# PSU.net
KiCad netlist of a schematic drawn in EAGLE
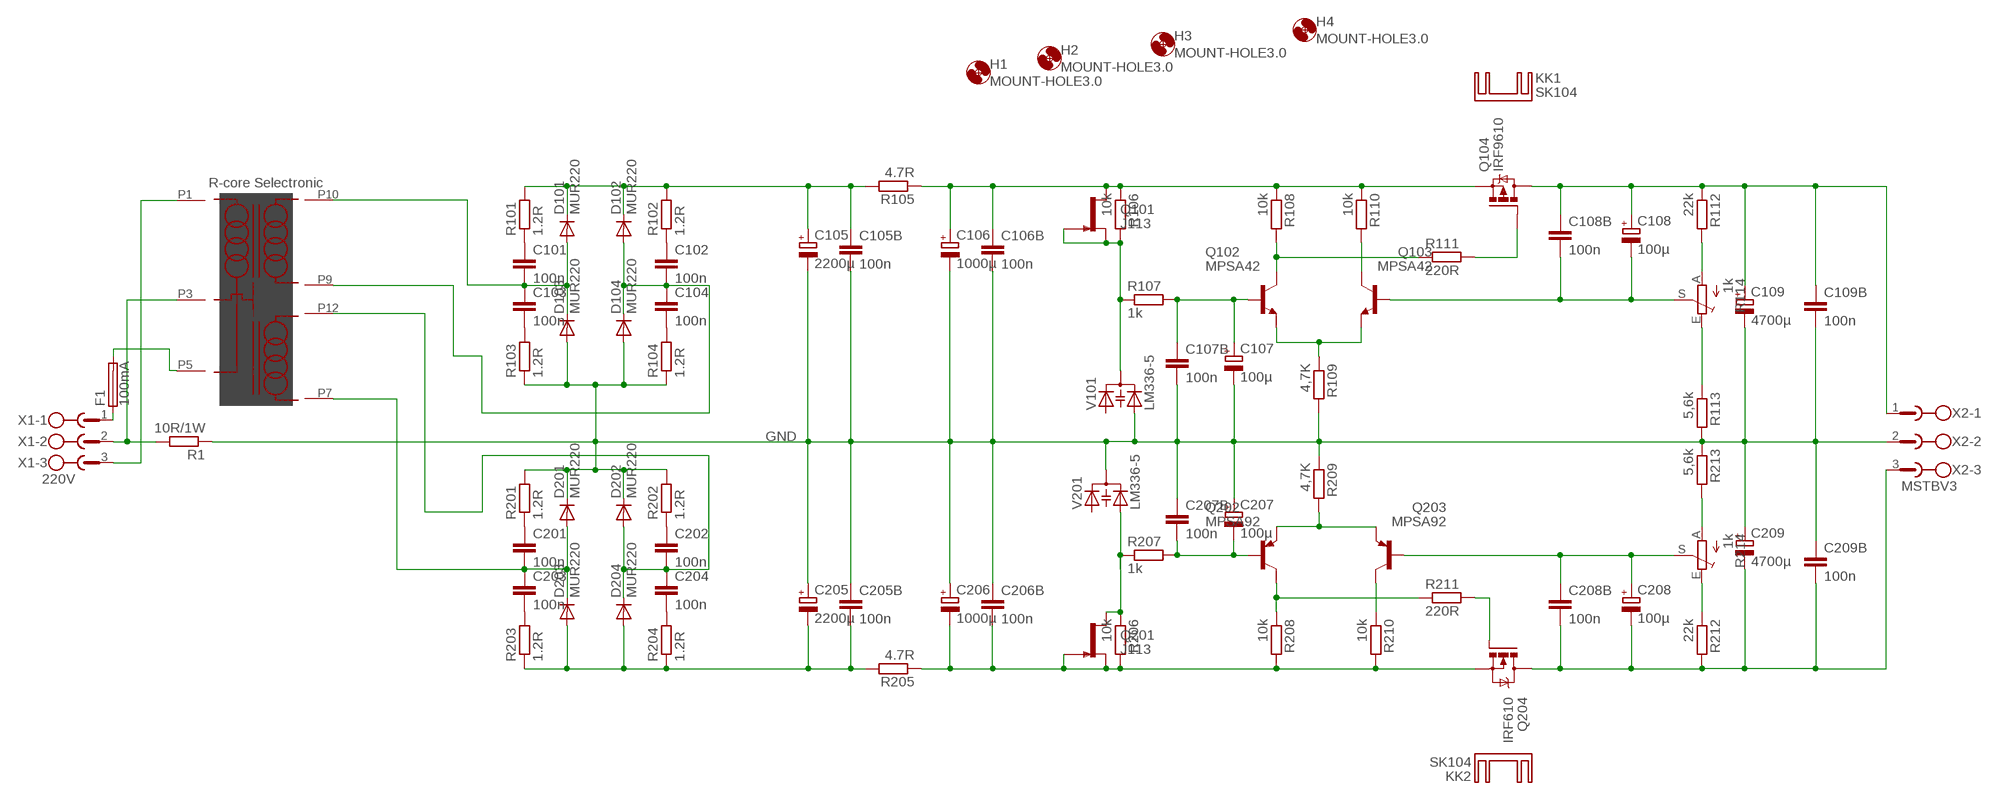
[diagram p0: schematic, sheet 1]

(export (version "E")
  (design (tool "Eeschema 10.0.6"))
  (components
    (comp (ref "C101")
      (value "100n")
      (footprint "eagle-import:C050-025X075")
      (libsource (lib "eagle-import") (part "C-EU050-025X075"))
    )
    (comp (ref "C102")
      (value "100n")
      (footprint "eagle-import:C050-025X075")
      (libsource (lib "eagle-import") (part "C-EU050-025X075"))
    )
    (comp (ref "C103")
      (value "100n")
      (footprint "eagle-import:C050-025X075")
      (libsource (lib "eagle-import") (part "C-EU050-025X075"))
    )
    (comp (ref "C104")
      (value "100n")
      (footprint "eagle-import:C050-025X075")
      (libsource (lib "eagle-import") (part "C-EU050-025X075"))
    )
    (comp (ref "C105")
      (value "2200µ")
      (footprint "eagle-import:E7,5-16")
      (libsource (lib "eagle-import") (part "CPOL-EUE7.5-16"))
    )
    (comp (ref "C105B")
      (value "100n")
      (footprint "eagle-import:C050-025X075")
      (libsource (lib "eagle-import") (part "C-EU050-025X075"))
    )
    (comp (ref "C106")
      (value "1000µ")
      (footprint "eagle-import:E7,5-16")
      (libsource (lib "eagle-import") (part "CPOL-EUE7.5-16"))
    )
    (comp (ref "C106B")
      (value "100n")
      (footprint "eagle-import:C050-025X075")
      (libsource (lib "eagle-import") (part "C-EU050-025X075"))
    )
    (comp (ref "C107")
      (value "100µ")
      (footprint "eagle-import:E5-10,5")
      (libsource (lib "eagle-import") (part "CPOL-EUE5-10.5"))
    )
    (comp (ref "C107B")
      (value "100n")
      (footprint "eagle-import:C050-025X075")
      (libsource (lib "eagle-import") (part "C-EU050-025X075"))
    )
    (comp (ref "C108")
      (value "100µ")
      (footprint "eagle-import:E5-10,5")
      (libsource (lib "eagle-import") (part "CPOL-EUE5-10.5"))
    )
    (comp (ref "C108B")
      (value "100n")
      (footprint "eagle-import:C050-025X075")
      (libsource (lib "eagle-import") (part "C-EU050-025X075"))
    )
    (comp (ref "C109")
      (value "4700µ")
      (footprint "eagle-import:EB25D")
      (libsource (lib "eagle-import") (part "CPOL-EUE10-25"))
    )
    (comp (ref "C109B")
      (value "100n")
      (footprint "eagle-import:C050-025X075")
      (libsource (lib "eagle-import") (part "C-EU050-025X075"))
    )
    (comp (ref "C201")
      (value "100n")
      (footprint "eagle-import:C050-025X075")
      (libsource (lib "eagle-import") (part "C-EU050-025X075"))
    )
    (comp (ref "C202")
      (value "100n")
      (footprint "eagle-import:C050-025X075")
      (libsource (lib "eagle-import") (part "C-EU050-025X075"))
    )
    (comp (ref "C203")
      (value "100n")
      (footprint "eagle-import:C050-025X075")
      (libsource (lib "eagle-import") (part "C-EU050-025X075"))
    )
    (comp (ref "C204")
      (value "100n")
      (footprint "eagle-import:C050-025X075")
      (libsource (lib "eagle-import") (part "C-EU050-025X075"))
    )
    (comp (ref "C205")
      (value "2200µ")
      (footprint "eagle-import:E7,5-16")
      (libsource (lib "eagle-import") (part "CPOL-EUE7.5-16"))
    )
    (comp (ref "C205B")
      (value "100n")
      (footprint "eagle-import:C050-025X075")
      (libsource (lib "eagle-import") (part "C-EU050-025X075"))
    )
    (comp (ref "C206")
      (value "1000µ")
      (footprint "eagle-import:E7,5-16")
      (libsource (lib "eagle-import") (part "CPOL-EUE7.5-16"))
    )
    (comp (ref "C206B")
      (value "100n")
      (footprint "eagle-import:C050-025X075")
      (libsource (lib "eagle-import") (part "C-EU050-025X075"))
    )
    (comp (ref "C207")
      (value "100µ")
      (footprint "eagle-import:E5-10,5")
      (libsource (lib "eagle-import") (part "CPOL-EUE5-10.5"))
    )
    (comp (ref "C207B")
      (value "100n")
      (footprint "eagle-import:C050-025X075")
      (libsource (lib "eagle-import") (part "C-EU050-025X075"))
    )
    (comp (ref "C208")
      (value "100µ")
      (footprint "eagle-import:E5-10,5")
      (libsource (lib "eagle-import") (part "CPOL-EUE5-10.5"))
    )
    (comp (ref "C208B")
      (value "100n")
      (footprint "eagle-import:C050-025X075")
      (libsource (lib "eagle-import") (part "C-EU050-025X075"))
    )
    (comp (ref "C209")
      (value "4700µ")
      (footprint "eagle-import:EB25D")
      (libsource (lib "eagle-import") (part "CPOL-EUE10-25"))
    )
    (comp (ref "C209B")
      (value "100n")
      (footprint "eagle-import:C050-025X075")
      (libsource (lib "eagle-import") (part "C-EU050-025X075"))
    )
    (comp (ref "D101")
      (value "MUR220")
      (footprint "eagle-import:DO201-15")
      (libsource (lib "eagle-import") (part "BY500"))
    )
    (comp (ref "D102")
      (value "MUR220")
      (footprint "eagle-import:DO201-15")
      (libsource (lib "eagle-import") (part "BY500"))
    )
    (comp (ref "D103")
      (value "MUR220")
      (footprint "eagle-import:DO201-15")
      (libsource (lib "eagle-import") (part "BY500"))
    )
    (comp (ref "D104")
      (value "MUR220")
      (footprint "eagle-import:DO201-15")
      (libsource (lib "eagle-import") (part "BY500"))
    )
    (comp (ref "D201")
      (value "MUR220")
      (footprint "eagle-import:DO201-15")
      (libsource (lib "eagle-import") (part "BY500"))
    )
    (comp (ref "D202")
      (value "MUR220")
      (footprint "eagle-import:DO201-15")
      (libsource (lib "eagle-import") (part "BY500"))
    )
    (comp (ref "D203")
      (value "MUR220")
      (footprint "eagle-import:DO201-15")
      (libsource (lib "eagle-import") (part "BY500"))
    )
    (comp (ref "D204")
      (value "MUR220")
      (footprint "eagle-import:DO201-15")
      (libsource (lib "eagle-import") (part "BY500"))
    )
    (comp (ref "F1")
      (value "100mA")
      (footprint "eagle-import:GSH15")
      (fields (field (name "MPN") "64900001039"))
      (libsource (lib "eagle-import") (part "GSH15"))
    )
    (comp (ref "H1")
      (value "MOUNT-HOLE3.0")
      (footprint "eagle-import:3,0")
      (libsource (lib "eagle-import") (part "MOUNT-HOLE3.0"))
    )
    (comp (ref "H2")
      (value "MOUNT-HOLE3.0")
      (footprint "eagle-import:3,0")
      (libsource (lib "eagle-import") (part "MOUNT-HOLE3.0"))
    )
    (comp (ref "H3")
      (value "MOUNT-HOLE3.0")
      (footprint "eagle-import:3,0")
      (libsource (lib "eagle-import") (part "MOUNT-HOLE3.0"))
    )
    (comp (ref "H4")
      (value "MOUNT-HOLE3.0")
      (footprint "eagle-import:3,0")
      (libsource (lib "eagle-import") (part "MOUNT-HOLE3.0"))
    )
    (comp (ref "KK1")
      (value "SK104")
      (footprint "eagle-import:SK104")
      (libsource (lib "eagle-import") (part "SK104"))
    )
    (comp (ref "KK2")
      (value "SK104")
      (footprint "eagle-import:SK104")
      (libsource (lib "eagle-import") (part "SK104"))
    )
    (comp (ref "Q101")
      (value "J113")
      (footprint "eagle-import:TO-92")
      (libsource (lib "eagle-import") (part "2N5458"))
    )
    (comp (ref "Q102")
      (value "MPSA42")
      (footprint "eagle-import:TO92-EBC")
      (libsource (lib "eagle-import") (part "-NPN-TO92-EBC"))
    )
    (comp (ref "Q103")
      (value "MPSA42")
      (footprint "eagle-import:TO92-EBC")
      (libsource (lib "eagle-import") (part "-NPN-TO92-EBC"))
    )
    (comp (ref "Q104")
      (value "IRF9610")
      (footprint "eagle-import:TO220BV")
      (libsource (lib "eagle-import") (part "IRF9530"))
    )
    (comp (ref "Q201")
      (value "J113")
      (footprint "eagle-import:TO-92")
      (libsource (lib "eagle-import") (part "2N5458"))
    )
    (comp (ref "Q202")
      (value "MPSA92")
      (footprint "eagle-import:TO92-EBC")
      (libsource (lib "eagle-import") (part "-PNP-TO92-EBCBCX58"))
    )
    (comp (ref "Q203")
      (value "MPSA92")
      (footprint "eagle-import:TO92-EBC")
      (libsource (lib "eagle-import") (part "-PNP-TO92-EBCBCX58"))
    )
    (comp (ref "Q204")
      (value "IRF610")
      (footprint "eagle-import:TO220BV")
      (libsource (lib "eagle-import") (part "IRF740"))
    )
    (comp (ref "R1")
      (value "10R/1W")
      (footprint "eagle-import:P0613_15")
      (libsource (lib "eagle-import") (part "R-EU_0613/15"))
    )
    (comp (ref "R101")
      (value "1.2R")
      (footprint "eagle-import:0207_10")
      (libsource (lib "eagle-import") (part "R-EU_0207/10"))
    )
    (comp (ref "R102")
      (value "1.2R")
      (footprint "eagle-import:0207_10")
      (libsource (lib "eagle-import") (part "R-EU_0207/10"))
    )
    (comp (ref "R103")
      (value "1.2R")
      (footprint "eagle-import:0207_10")
      (libsource (lib "eagle-import") (part "R-EU_0207/10"))
    )
    (comp (ref "R104")
      (value "1.2R")
      (footprint "eagle-import:0207_10")
      (libsource (lib "eagle-import") (part "R-EU_0207/10"))
    )
    (comp (ref "R105")
      (value "4.7R")
      (footprint "eagle-import:0207_10")
      (libsource (lib "eagle-import") (part "R-EU_0207/10"))
    )
    (comp (ref "R106")
      (value "10k")
      (footprint "eagle-import:0207_10")
      (libsource (lib "eagle-import") (part "R-EU_0207/10"))
    )
    (comp (ref "R107")
      (value "1k")
      (footprint "eagle-import:0207_10")
      (libsource (lib "eagle-import") (part "R-EU_0207/10"))
    )
    (comp (ref "R108")
      (value "10k")
      (footprint "eagle-import:0207_10")
      (libsource (lib "eagle-import") (part "R-EU_0207/10"))
    )
    (comp (ref "R109")
      (value "4,7K")
      (footprint "eagle-import:0207_10")
      (libsource (lib "eagle-import") (part "R-EU_0207/10"))
    )
    (comp (ref "R110")
      (value "10k")
      (footprint "eagle-import:0207_10")
      (libsource (lib "eagle-import") (part "R-EU_0207/10"))
    )
    (comp (ref "R111")
      (value "220R")
      (footprint "eagle-import:0207_10")
      (libsource (lib "eagle-import") (part "R-EU_0207/10"))
    )
    (comp (ref "R112")
      (value "22k")
      (footprint "eagle-import:0207_10")
      (libsource (lib "eagle-import") (part "R-EU_0207/10"))
    )
    (comp (ref "R113")
      (value "5,6k")
      (footprint "eagle-import:0207_10")
      (libsource (lib "eagle-import") (part "R-EU_0207/10"))
    )
    (comp (ref "R114")
      (value "1k")
      (footprint "eagle-import:S64W")
      (libsource (lib "eagle-import") (part "TRIM_EU-S64W"))
    )
    (comp (ref "R201")
      (value "1.2R")
      (footprint "eagle-import:0207_10")
      (libsource (lib "eagle-import") (part "R-EU_0207/10"))
    )
    (comp (ref "R202")
      (value "1.2R")
      (footprint "eagle-import:0207_10")
      (libsource (lib "eagle-import") (part "R-EU_0207/10"))
    )
    (comp (ref "R203")
      (value "1.2R")
      (footprint "eagle-import:0207_10")
      (libsource (lib "eagle-import") (part "R-EU_0207/10"))
    )
    (comp (ref "R204")
      (value "1.2R")
      (footprint "eagle-import:0207_10")
      (libsource (lib "eagle-import") (part "R-EU_0207/10"))
    )
    (comp (ref "R205")
      (value "4.7R")
      (footprint "eagle-import:0207_10")
      (libsource (lib "eagle-import") (part "R-EU_0207/10"))
    )
    (comp (ref "R206")
      (value "10k")
      (footprint "eagle-import:0207_10")
      (libsource (lib "eagle-import") (part "R-EU_0207/10"))
    )
    (comp (ref "R207")
      (value "1k")
      (footprint "eagle-import:0207_10")
      (libsource (lib "eagle-import") (part "R-EU_0207/10"))
    )
    (comp (ref "R208")
      (value "10k")
      (footprint "eagle-import:0207_10")
      (libsource (lib "eagle-import") (part "R-EU_0207/10"))
    )
    (comp (ref "R209")
      (value "4,7K")
      (footprint "eagle-import:0207_10")
      (libsource (lib "eagle-import") (part "R-EU_0207/10"))
    )
    (comp (ref "R210")
      (value "10k")
      (footprint "eagle-import:0207_10")
      (libsource (lib "eagle-import") (part "R-EU_0207/10"))
    )
    (comp (ref "R211")
      (value "220R")
      (footprint "eagle-import:0207_10")
      (libsource (lib "eagle-import") (part "R-EU_0207/10"))
    )
    (comp (ref "R212")
      (value "22k")
      (footprint "eagle-import:0207_10")
      (libsource (lib "eagle-import") (part "R-EU_0207/10"))
    )
    (comp (ref "R213")
      (value "5,6k")
      (footprint "eagle-import:0207_10")
      (libsource (lib "eagle-import") (part "R-EU_0207/10"))
    )
    (comp (ref "R214")
      (value "1k")
      (footprint "eagle-import:S64W")
      (libsource (lib "eagle-import") (part "TRIM_EU-S64W"))
    )
    (comp (ref "U$1")
      (value "R-CORE-SELECTRONIC-PCB")
      (footprint "eagle-import:R-CORE48MM")
      (libsource (lib "eagle-import") (part "R-CORE-SELECTRONIC-PCB"))
    )
    (comp (ref "V101")
      (value "LM336-5")
      (footprint "eagle-import:SOT54E")
      (libsource (lib "eagle-import") (part "DIODE-2CAPACITANCESOT54E"))
    )
    (comp (ref "V201")
      (value "LM336-5")
      (footprint "eagle-import:SOT54E")
      (libsource (lib "eagle-import") (part "DIODE-2CAPACITANCESOT54E"))
    )
    (comp (ref "X1")
      (value "220V")
      (footprint "eagle-import:MSTBV3")
      (fields (field (name "MPN") "MSTBV 2,5/3-GF-5.08"))
      (libsource (lib "eagle-import") (part "MSTBV3"))
    )
    (comp (ref "X2")
      (value "MSTBV3")
      (footprint "eagle-import:MSTBV3")
      (fields (field (name "MPN") "MSTBV 2,5/3-GF-5.08"))
      (libsource (lib "eagle-import") (part "MSTBV3"))
    )
  )
  (nets
    (net (code "1") (name "/GND") (class "Default")
      (node (ref "C105") (pin "-") (pinfunction "-_-") (pintype "passive"))
      (node (ref "C105B") (pin "2") (pinfunction "2_2") (pintype "passive"))
      (node (ref "C106") (pin "-") (pinfunction "-_-") (pintype "passive"))
      (node (ref "C106B") (pin "2") (pinfunction "2_2") (pintype "passive"))
      (node (ref "C107") (pin "-") (pinfunction "-_-") (pintype "passive"))
      (node (ref "C107B") (pin "2") (pinfunction "2_2") (pintype "passive"))
      (node (ref "C109") (pin "-") (pinfunction "-_-") (pintype "passive"))
      (node (ref "C109B") (pin "2") (pinfunction "2_2") (pintype "passive"))
      (node (ref "C205") (pin "+") (pinfunction "+_+") (pintype "passive"))
      (node (ref "C205B") (pin "1") (pinfunction "1_1") (pintype "passive"))
      (node (ref "C206") (pin "+") (pinfunction "+_+") (pintype "passive"))
      (node (ref "C206B") (pin "1") (pinfunction "1_1") (pintype "passive"))
      (node (ref "C207") (pin "+") (pinfunction "+_+") (pintype "passive"))
      (node (ref "C207B") (pin "1") (pinfunction "1_1") (pintype "passive"))
      (node (ref "C209") (pin "+") (pinfunction "+_+") (pintype "passive"))
      (node (ref "C209B") (pin "1") (pinfunction "1_1") (pintype "passive"))
      (node (ref "D103") (pin "A") (pinfunction "A_A") (pintype "passive"))
      (node (ref "D104") (pin "A") (pinfunction "A_A") (pintype "passive"))
      (node (ref "D201") (pin "C") (pinfunction "C_C") (pintype "passive"))
      (node (ref "D202") (pin "C") (pinfunction "C_C") (pintype "passive"))
      (node (ref "R1") (pin "1") (pinfunction "1_1") (pintype "passive"))
      (node (ref "R103") (pin "1") (pinfunction "1_1") (pintype "passive"))
      (node (ref "R104") (pin "1") (pinfunction "1_1") (pintype "passive"))
      (node (ref "R109") (pin "2") (pinfunction "2_2") (pintype "passive"))
      (node (ref "R113") (pin "2") (pinfunction "2_2") (pintype "passive"))
      (node (ref "R201") (pin "2") (pinfunction "2_2") (pintype "passive"))
      (node (ref "R202") (pin "2") (pinfunction "2_2") (pintype "passive"))
      (node (ref "R209") (pin "1") (pinfunction "1_1") (pintype "passive"))
      (node (ref "R213") (pin "1") (pinfunction "1_1") (pintype "passive"))
      (node (ref "V101") (pin "A2") (pinfunction "A2_A2") (pintype "passive"))
      (node (ref "V201") (pin "C") (pinfunction "C_C") (pintype "passive"))
      (node (ref "X2") (pin "2") (pinfunction "1_2") (pintype "passive"))
    )
    (net (code "2") (name "Net-(C101-Pad1)") (class "Default")
      (node (ref "C101") (pin "1") (pinfunction "1_1") (pintype "passive"))
      (node (ref "R101") (pin "1") (pinfunction "1_1") (pintype "passive"))
    )
    (net (code "3") (name "Net-(C102-Pad1)") (class "Default")
      (node (ref "C102") (pin "1") (pinfunction "1_1") (pintype "passive"))
      (node (ref "R102") (pin "1") (pinfunction "1_1") (pintype "passive"))
    )
    (net (code "4") (name "Net-(C103-Pad2)") (class "Default")
      (node (ref "C103") (pin "2") (pinfunction "2_2") (pintype "passive"))
      (node (ref "R103") (pin "2") (pinfunction "2_2") (pintype "passive"))
    )
    (net (code "5") (name "Net-(C104-Pad2)") (class "Default")
      (node (ref "C104") (pin "2") (pinfunction "2_2") (pintype "passive"))
      (node (ref "R104") (pin "2") (pinfunction "2_2") (pintype "passive"))
    )
    (net (code "6") (name "Net-(C105-Pad+)") (class "Default")
      (node (ref "C105") (pin "+") (pinfunction "+_+") (pintype "passive"))
      (node (ref "C105B") (pin "1") (pinfunction "1_1") (pintype "passive"))
      (node (ref "D101") (pin "C") (pinfunction "C_C") (pintype "passive"))
      (node (ref "D102") (pin "C") (pinfunction "C_C") (pintype "passive"))
      (node (ref "R101") (pin "2") (pinfunction "2_2") (pintype "passive"))
      (node (ref "R102") (pin "2") (pinfunction "2_2") (pintype "passive"))
      (node (ref "R105") (pin "2") (pinfunction "2_2") (pintype "passive"))
    )
    (net (code "7") (name "Net-(C107-Pad+)") (class "Default")
      (node (ref "C107") (pin "+") (pinfunction "+_+") (pintype "passive"))
      (node (ref "C107B") (pin "1") (pinfunction "1_1") (pintype "passive"))
      (node (ref "Q102") (pin "B") (pinfunction "B_B") (pintype "passive"))
      (node (ref "R107") (pin "2") (pinfunction "2_2") (pintype "passive"))
    )
    (net (code "8") (name "Net-(C108-Pad+)") (class "Default")
      (node (ref "C108") (pin "+") (pinfunction "+_+") (pintype "passive"))
      (node (ref "C108B") (pin "1") (pinfunction "1_1") (pintype "passive"))
      (node (ref "C109") (pin "+") (pinfunction "+_+") (pintype "passive"))
      (node (ref "C109B") (pin "1") (pinfunction "1_1") (pintype "passive"))
      (node (ref "Q104") (pin "D") (pinfunction "D_D") (pintype "passive"))
      (node (ref "R112") (pin "1") (pinfunction "1_1") (pintype "passive"))
      (node (ref "X2") (pin "1") (pinfunction "1_1") (pintype "passive"))
    )
    (net (code "9") (name "Net-(C108-Pad-)") (class "Default")
      (node (ref "C108") (pin "-") (pinfunction "-_-") (pintype "passive"))
      (node (ref "C108B") (pin "2") (pinfunction "2_2") (pintype "passive"))
      (node (ref "Q103") (pin "B") (pinfunction "B_B") (pintype "passive"))
      (node (ref "R114") (pin "S") (pinfunction "S_S") (pintype "passive"))
    )
    (net (code "10") (name "Net-(C201-Pad1)") (class "Default")
      (node (ref "C201") (pin "1") (pinfunction "1_1") (pintype "passive"))
      (node (ref "R201") (pin "1") (pinfunction "1_1") (pintype "passive"))
    )
    (net (code "11") (name "Net-(C202-Pad1)") (class "Default")
      (node (ref "C202") (pin "1") (pinfunction "1_1") (pintype "passive"))
      (node (ref "R202") (pin "1") (pinfunction "1_1") (pintype "passive"))
    )
    (net (code "12") (name "Net-(C203-Pad2)") (class "Default")
      (node (ref "C203") (pin "2") (pinfunction "2_2") (pintype "passive"))
      (node (ref "R203") (pin "2") (pinfunction "2_2") (pintype "passive"))
    )
    (net (code "13") (name "Net-(C204-Pad2)") (class "Default")
      (node (ref "C204") (pin "2") (pinfunction "2_2") (pintype "passive"))
      (node (ref "R204") (pin "2") (pinfunction "2_2") (pintype "passive"))
    )
    (net (code "14") (name "Net-(C205-Pad-)") (class "Default")
      (node (ref "C205") (pin "-") (pinfunction "-_-") (pintype "passive"))
      (node (ref "C205B") (pin "2") (pinfunction "2_2") (pintype "passive"))
      (node (ref "D203") (pin "A") (pinfunction "A_A") (pintype "passive"))
      (node (ref "D204") (pin "A") (pinfunction "A_A") (pintype "passive"))
      (node (ref "R203") (pin "1") (pinfunction "1_1") (pintype "passive"))
      (node (ref "R204") (pin "1") (pinfunction "1_1") (pintype "passive"))
      (node (ref "R205") (pin "2") (pinfunction "2_2") (pintype "passive"))
    )
    (net (code "15") (name "Net-(C207-Pad-)") (class "Default")
      (node (ref "C207") (pin "-") (pinfunction "-_-") (pintype "passive"))
      (node (ref "C207B") (pin "2") (pinfunction "2_2") (pintype "passive"))
      (node (ref "Q202") (pin "B") (pinfunction "B_B") (pintype "passive"))
      (node (ref "R207") (pin "2") (pinfunction "2_2") (pintype "passive"))
    )
    (net (code "16") (name "Net-(C208-Pad+)") (class "Default")
      (node (ref "C208") (pin "+") (pinfunction "+_+") (pintype "passive"))
      (node (ref "C208B") (pin "1") (pinfunction "1_1") (pintype "passive"))
      (node (ref "Q203") (pin "B") (pinfunction "B_B") (pintype "passive"))
      (node (ref "R214") (pin "S") (pinfunction "S_S") (pintype "passive"))
    )
    (net (code "17") (name "Net-(F1-Pad1)") (class "Default")
      (node (ref "F1") (pin "1") (pinfunction "1_1") (pintype "passive"))
      (node (ref "X1") (pin "1") (pinfunction "1_1") (pintype "passive"))
    )
    (net (code "18") (name "Net-(Q101-D)") (class "Default")
      (node (ref "C106") (pin "+") (pinfunction "+_+") (pintype "passive"))
      (node (ref "C106B") (pin "1") (pinfunction "1_1") (pintype "passive"))
      (node (ref "Q101") (pin "1") (pinfunction "D_1") (pintype "passive"))
      (node (ref "Q104") (pin "S") (pinfunction "S_S") (pintype "passive"))
      (node (ref "R105") (pin "1") (pinfunction "1_1") (pintype "passive"))
      (node (ref "R106") (pin "1") (pinfunction "1_1") (pintype "passive"))
      (node (ref "R108") (pin "1") (pinfunction "1_1") (pintype "passive"))
      (node (ref "R110") (pin "1") (pinfunction "1_1") (pintype "passive"))
    )
    (net (code "19") (name "Net-(Q101-G)") (class "Default")
      (node (ref "Q101") (pin "2") (pinfunction "S_2") (pintype "passive"))
      (node (ref "Q101") (pin "3") (pinfunction "G_3") (pintype "passive"))
      (node (ref "R106") (pin "2") (pinfunction "2_2") (pintype "passive"))
      (node (ref "R107") (pin "1") (pinfunction "1_1") (pintype "passive"))
      (node (ref "V101") (pin "C") (pinfunction "C_C") (pintype "passive"))
    )
    (net (code "20") (name "Net-(Q102-PadC)") (class "Default")
      (node (ref "Q102") (pin "C") (pinfunction "C_C") (pintype "passive"))
      (node (ref "R108") (pin "2") (pinfunction "2_2") (pintype "passive"))
      (node (ref "R111") (pin "1") (pinfunction "1_1") (pintype "passive"))
    )
    (net (code "21") (name "Net-(Q102-PadE)") (class "Default")
      (node (ref "Q102") (pin "E") (pinfunction "E_E") (pintype "passive"))
      (node (ref "Q103") (pin "E") (pinfunction "E_E") (pintype "passive"))
      (node (ref "R109") (pin "1") (pinfunction "1_1") (pintype "passive"))
    )
    (net (code "22") (name "Net-(Q103-PadC)") (class "Default")
      (node (ref "Q103") (pin "C") (pinfunction "C_C") (pintype "passive"))
      (node (ref "R110") (pin "2") (pinfunction "2_2") (pintype "passive"))
    )
    (net (code "23") (name "Net-(Q104-PadG)") (class "Default")
      (node (ref "Q104") (pin "G") (pinfunction "G_G") (pintype "passive"))
      (node (ref "R111") (pin "2") (pinfunction "2_2") (pintype "passive"))
    )
    (net (code "24") (name "Net-(Q201-D)") (class "Default")
      (node (ref "Q201") (pin "1") (pinfunction "D_1") (pintype "passive"))
      (node (ref "R206") (pin "1") (pinfunction "1_1") (pintype "passive"))
      (node (ref "R207") (pin "1") (pinfunction "1_1") (pintype "passive"))
      (node (ref "V201") (pin "A2") (pinfunction "A2_A2") (pintype "passive"))
    )
    (net (code "25") (name "Net-(Q201-G)") (class "Default")
      (node (ref "C206") (pin "-") (pinfunction "-_-") (pintype "passive"))
      (node (ref "C206B") (pin "2") (pinfunction "2_2") (pintype "passive"))
      (node (ref "Q201") (pin "2") (pinfunction "S_2") (pintype "passive"))
      (node (ref "Q201") (pin "3") (pinfunction "G_3") (pintype "passive"))
      (node (ref "Q204") (pin "S") (pinfunction "S_S") (pintype "passive"))
      (node (ref "R205") (pin "1") (pinfunction "1_1") (pintype "passive"))
      (node (ref "R206") (pin "2") (pinfunction "2_2") (pintype "passive"))
      (node (ref "R208") (pin "2") (pinfunction "2_2") (pintype "passive"))
      (node (ref "R210") (pin "2") (pinfunction "2_2") (pintype "passive"))
    )
    (net (code "26") (name "Net-(Q202-PadC)") (class "Default")
      (node (ref "Q202") (pin "C") (pinfunction "C_C") (pintype "passive"))
      (node (ref "R208") (pin "1") (pinfunction "1_1") (pintype "passive"))
      (node (ref "R211") (pin "1") (pinfunction "1_1") (pintype "passive"))
    )
    (net (code "27") (name "Net-(Q202-PadE)") (class "Default")
      (node (ref "Q202") (pin "E") (pinfunction "E_E") (pintype "passive"))
      (node (ref "Q203") (pin "E") (pinfunction "E_E") (pintype "passive"))
      (node (ref "R209") (pin "2") (pinfunction "2_2") (pintype "passive"))
    )
    (net (code "28") (name "Net-(Q203-PadC)") (class "Default")
      (node (ref "Q203") (pin "C") (pinfunction "C_C") (pintype "passive"))
      (node (ref "R210") (pin "1") (pinfunction "1_1") (pintype "passive"))
    )
    (net (code "29") (name "Net-(Q204-PadG)") (class "Default")
      (node (ref "Q204") (pin "G") (pinfunction "G_G") (pintype "passive"))
      (node (ref "R211") (pin "2") (pinfunction "2_2") (pintype "passive"))
    )
    (net (code "30") (name "Net-(R112-Pad2)") (class "Default")
      (node (ref "R112") (pin "2") (pinfunction "2_2") (pintype "passive"))
      (node (ref "R114") (pin "A") (pinfunction "A_A") (pintype "passive"))
    )
    (net (code "31") (name "Net-(R113-Pad1)") (class "Default")
      (node (ref "R113") (pin "1") (pinfunction "1_1") (pintype "passive"))
      (node (ref "R114") (pin "E") (pinfunction "E_E") (pintype "passive"))
    )
    (net (code "32") (name "Net-(R212-Pad1)") (class "Default")
      (node (ref "R212") (pin "1") (pinfunction "1_1") (pintype "passive"))
      (node (ref "R214") (pin "E") (pinfunction "E_E") (pintype "passive"))
    )
    (net (code "33") (name "Net-(R213-Pad2)") (class "Default")
      (node (ref "R213") (pin "2") (pinfunction "2_2") (pintype "passive"))
      (node (ref "R214") (pin "A") (pinfunction "A_A") (pintype "passive"))
    )
    (net (code "34") (name "Net-(U$1-PRIM-1)") (class "Default")
      (node (ref "U$1") (pin "P1") (pinfunction "PRIM-1_P1") (pintype "bidirectional"))
      (node (ref "X1") (pin "3") (pinfunction "1_3") (pintype "passive"))
    )
    (net (code "35") (name "Net-(U$1-PRIM5)") (class "Default")
      (node (ref "F1") (pin "2") (pinfunction "2_2") (pintype "passive"))
      (node (ref "U$1") (pin "P5") (pinfunction "PRIM5_P5") (pintype "bidirectional"))
    )
    (net (code "36") (name "Net-(U$1-SEC1-7)") (class "Default")
      (node (ref "C201") (pin "2") (pinfunction "2_2") (pintype "passive"))
      (node (ref "C203") (pin "1") (pinfunction "1_1") (pintype "passive"))
      (node (ref "D201") (pin "A") (pinfunction "A_A") (pintype "passive"))
      (node (ref "D203") (pin "C") (pinfunction "C_C") (pintype "passive"))
      (node (ref "U$1") (pin "P7") (pinfunction "SEC1-7_P7") (pintype "bidirectional"))
    )
    (net (code "37") (name "Net-(U$1-SEC1-12)") (class "Default")
      (node (ref "C202") (pin "2") (pinfunction "2_2") (pintype "passive"))
      (node (ref "C204") (pin "1") (pinfunction "1_1") (pintype "passive"))
      (node (ref "D202") (pin "A") (pinfunction "A_A") (pintype "passive"))
      (node (ref "D204") (pin "C") (pinfunction "C_C") (pintype "passive"))
      (node (ref "U$1") (pin "P12") (pinfunction "SEC1-12_P12") (pintype "bidirectional"))
    )
    (net (code "38") (name "Net-(U$1-SEC2-9)") (class "Default")
      (node (ref "C102") (pin "2") (pinfunction "2_2") (pintype "passive"))
      (node (ref "C104") (pin "1") (pinfunction "1_1") (pintype "passive"))
      (node (ref "D102") (pin "A") (pinfunction "A_A") (pintype "passive"))
      (node (ref "D104") (pin "C") (pinfunction "C_C") (pintype "passive"))
      (node (ref "U$1") (pin "P9") (pinfunction "SEC2-9_P9") (pintype "bidirectional"))
    )
    (net (code "39") (name "Net-(U$1-SEC2-10)") (class "Default")
      (node (ref "C101") (pin "2") (pinfunction "2_2") (pintype "passive"))
      (node (ref "C103") (pin "1") (pinfunction "1_1") (pintype "passive"))
      (node (ref "D101") (pin "A") (pinfunction "A_A") (pintype "passive"))
      (node (ref "D103") (pin "C") (pinfunction "C_C") (pintype "passive"))
      (node (ref "U$1") (pin "P10") (pinfunction "SEC2-10_P10") (pintype "bidirectional"))
    )
    (net (code "40") (name "Net-(U$1-SHIELD3)") (class "Default")
      (node (ref "R1") (pin "2") (pinfunction "2_2") (pintype "passive"))
      (node (ref "U$1") (pin "P3") (pinfunction "SHIELD3_P3") (pintype "bidirectional"))
      (node (ref "X1") (pin "2") (pinfunction "1_2") (pintype "passive"))
    )
    (net (code "41") (name "Net-(X2C-1)") (class "Default")
      (node (ref "C208") (pin "-") (pinfunction "-_-") (pintype "passive"))
      (node (ref "C208B") (pin "2") (pinfunction "2_2") (pintype "passive"))
      (node (ref "C209") (pin "-") (pinfunction "-_-") (pintype "passive"))
      (node (ref "C209B") (pin "2") (pinfunction "2_2") (pintype "passive"))
      (node (ref "Q204") (pin "D") (pinfunction "D_D") (pintype "passive"))
      (node (ref "R212") (pin "2") (pinfunction "2_2") (pintype "passive"))
      (node (ref "X2") (pin "3") (pinfunction "1_3") (pintype "passive"))
    )
    (net (code "42") (name "unconnected-(V101-PadA1)") (class "Default")
      (node (ref "V101") (pin "A1") (pinfunction "A1_A1") (pintype "passive"))
    )
    (net (code "43") (name "unconnected-(V201-PadA1)") (class "Default")
      (node (ref "V201") (pin "A1") (pinfunction "A1_A1") (pintype "passive"))
    )
  )
)
